# Expand.net
KiCad netlist of a schematic drawn in Altium Designer
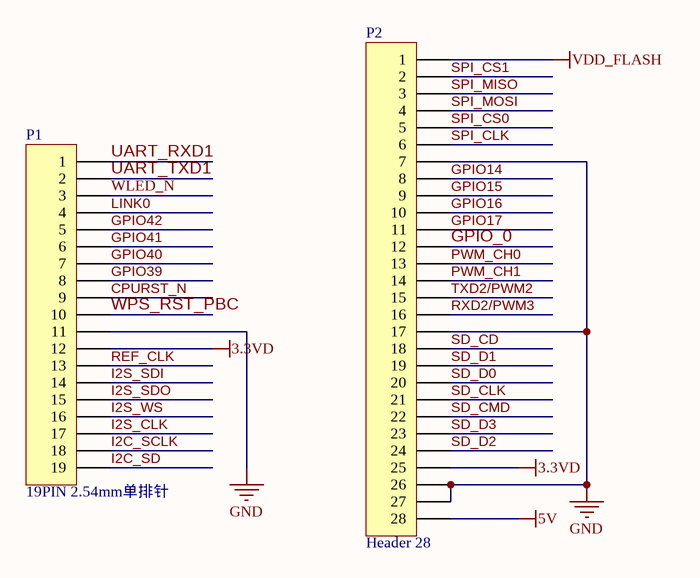
[diagram p0: Expand.SchDoc]

(export (version "E")
  (design (tool "Eeschema 10.0.6"))
  (components
    (comp (ref "P1")
      (value "19PIN 2.54mm单排针")
      (footprint "HDR1X19")
      (description "Header, 19-Pin")
      (fields (field (name "PUBLISHER") "Altium Limited"))
      (libsource (lib "LIB_MANGO") (part "Header 19"))
    )
    (comp (ref "P2")
      (value "Header 28")
      (footprint "HDR1X28")
      (description "Header, 28-Pin")
      (fields (field (name "PUBLISHER") "Altium Limited"))
      (libsource (lib "LIB_MANGO") (part "Header 28"))
    )
  )
  (nets
    (net (code "1") (name "/CPURST_N") (class "Default")
      (node (ref "P1") (pin "9") (pinfunction "9_9") (pintype "passive"))
    )
    (net (code "2") (name "/GPIO14") (class "Default")
      (node (ref "P2") (pin "8") (pinfunction "8_8") (pintype "passive"))
    )
    (net (code "3") (name "/GPIO15") (class "Default")
      (node (ref "P2") (pin "9") (pinfunction "9_9") (pintype "passive"))
    )
    (net (code "4") (name "/GPIO16") (class "Default")
      (node (ref "P2") (pin "10") (pinfunction "10_10") (pintype "passive"))
    )
    (net (code "5") (name "/GPIO17") (class "Default")
      (node (ref "P2") (pin "11") (pinfunction "11_11") (pintype "passive"))
    )
    (net (code "6") (name "/GPIO39") (class "Default")
      (node (ref "P1") (pin "8") (pinfunction "8_8") (pintype "passive"))
    )
    (net (code "7") (name "/GPIO40") (class "Default")
      (node (ref "P1") (pin "7") (pinfunction "7_7") (pintype "passive"))
    )
    (net (code "8") (name "/GPIO41") (class "Default")
      (node (ref "P1") (pin "6") (pinfunction "6_6") (pintype "passive"))
    )
    (net (code "9") (name "/GPIO42") (class "Default")
      (node (ref "P1") (pin "5") (pinfunction "5_5") (pintype "passive"))
    )
    (net (code "10") (name "/GPIO_0") (class "Default")
      (node (ref "P2") (pin "12") (pinfunction "12_12") (pintype "passive"))
    )
    (net (code "11") (name "/I2C_SCLK") (class "Default")
      (node (ref "P1") (pin "18") (pinfunction "18_18") (pintype "passive"))
    )
    (net (code "12") (name "/I2C_SD") (class "Default")
      (node (ref "P1") (pin "19") (pinfunction "19_19") (pintype "passive"))
    )
    (net (code "13") (name "/I2S_CLK") (class "Default")
      (node (ref "P1") (pin "17") (pinfunction "17_17") (pintype "passive"))
    )
    (net (code "14") (name "/I2S_SDI") (class "Default")
      (node (ref "P1") (pin "14") (pinfunction "14_14") (pintype "passive"))
    )
    (net (code "15") (name "/I2S_SDO") (class "Default")
      (node (ref "P1") (pin "15") (pinfunction "15_15") (pintype "passive"))
    )
    (net (code "16") (name "/I2S_WS") (class "Default")
      (node (ref "P1") (pin "16") (pinfunction "16_16") (pintype "passive"))
    )
    (net (code "17") (name "/LINK0") (class "Default")
      (node (ref "P1") (pin "4") (pinfunction "4_4") (pintype "passive"))
    )
    (net (code "18") (name "/PWM_CH0") (class "Default")
      (node (ref "P2") (pin "13") (pinfunction "13_13") (pintype "passive"))
    )
    (net (code "19") (name "/PWM_CH1") (class "Default")
      (node (ref "P2") (pin "14") (pinfunction "14_14") (pintype "passive"))
    )
    (net (code "20") (name "/REF_CLK") (class "Default")
      (node (ref "P1") (pin "13") (pinfunction "13_13") (pintype "passive"))
    )
    (net (code "21") (name "/RXD2{slash}PWM3") (class "Default")
      (node (ref "P2") (pin "16") (pinfunction "16_16") (pintype "passive"))
    )
    (net (code "22") (name "/SD_CD") (class "Default")
      (node (ref "P2") (pin "18") (pinfunction "18_18") (pintype "passive"))
    )
    (net (code "23") (name "/SD_CLK") (class "Default")
      (node (ref "P2") (pin "21") (pinfunction "21_21") (pintype "passive"))
    )
    (net (code "24") (name "/SD_CMD") (class "Default")
      (node (ref "P2") (pin "22") (pinfunction "22_22") (pintype "passive"))
    )
    (net (code "25") (name "/SD_D0") (class "Default")
      (node (ref "P2") (pin "20") (pinfunction "20_20") (pintype "passive"))
    )
    (net (code "26") (name "/SD_D1") (class "Default")
      (node (ref "P2") (pin "19") (pinfunction "19_19") (pintype "passive"))
    )
    (net (code "27") (name "/SD_D2") (class "Default")
      (node (ref "P2") (pin "24") (pinfunction "24_24") (pintype "passive"))
    )
    (net (code "28") (name "/SD_D3") (class "Default")
      (node (ref "P2") (pin "23") (pinfunction "23_23") (pintype "passive"))
    )
    (net (code "29") (name "/SPI_CLK") (class "Default")
      (node (ref "P2") (pin "6") (pinfunction "6_6") (pintype "passive"))
    )
    (net (code "30") (name "/SPI_CS0") (class "Default")
      (node (ref "P2") (pin "5") (pinfunction "5_5") (pintype "passive"))
    )
    (net (code "31") (name "/SPI_CS1") (class "Default")
      (node (ref "P2") (pin "2") (pinfunction "2_2") (pintype "passive"))
    )
    (net (code "32") (name "/SPI_MISO") (class "Default")
      (node (ref "P2") (pin "3") (pinfunction "3_3") (pintype "passive"))
    )
    (net (code "33") (name "/SPI_MOSI") (class "Default")
      (node (ref "P2") (pin "4") (pinfunction "4_4") (pintype "passive"))
    )
    (net (code "34") (name "/TXD2{slash}PWM2") (class "Default")
      (node (ref "P2") (pin "15") (pinfunction "15_15") (pintype "passive"))
    )
    (net (code "35") (name "/UART_RXD1") (class "Default")
      (node (ref "P1") (pin "1") (pinfunction "1_1") (pintype "passive"))
    )
    (net (code "36") (name "/UART_TXD1") (class "Default")
      (node (ref "P1") (pin "2") (pinfunction "2_2") (pintype "passive"))
    )
    (net (code "37") (name "/WLED_N") (class "Default")
      (node (ref "P1") (pin "3") (pinfunction "3_3") (pintype "passive"))
    )
    (net (code "38") (name "/WPS_RST_PBC") (class "Default")
      (node (ref "P1") (pin "10") (pinfunction "10_10") (pintype "passive"))
    )
    (net (code "39") (name "3.3VD") (class "Default")
      (node (ref "P1") (pin "12") (pinfunction "12_12") (pintype "passive"))
      (node (ref "P2") (pin "25") (pinfunction "25_25") (pintype "passive"))
    )
    (net (code "40") (name "5V") (class "Default")
      (node (ref "P2") (pin "28") (pinfunction "28_28") (pintype "passive"))
    )
    (net (code "41") (name "GND") (class "Default")
      (node (ref "P1") (pin "11") (pinfunction "11_11") (pintype "passive"))
      (node (ref "P2") (pin "17") (pinfunction "17_17") (pintype "passive"))
      (node (ref "P2") (pin "26") (pinfunction "26_26") (pintype "passive"))
      (node (ref "P2") (pin "27") (pinfunction "27_27") (pintype "passive"))
      (node (ref "P2") (pin "7") (pinfunction "7_7") (pintype "passive"))
    )
    (net (code "42") (name "VDD_FLASH") (class "Default")
      (node (ref "P2") (pin "1") (pinfunction "1_1") (pintype "passive"))
    )
  )
)
